# WattMeter.net
KiCad netlist of a schematic drawn in EAGLE
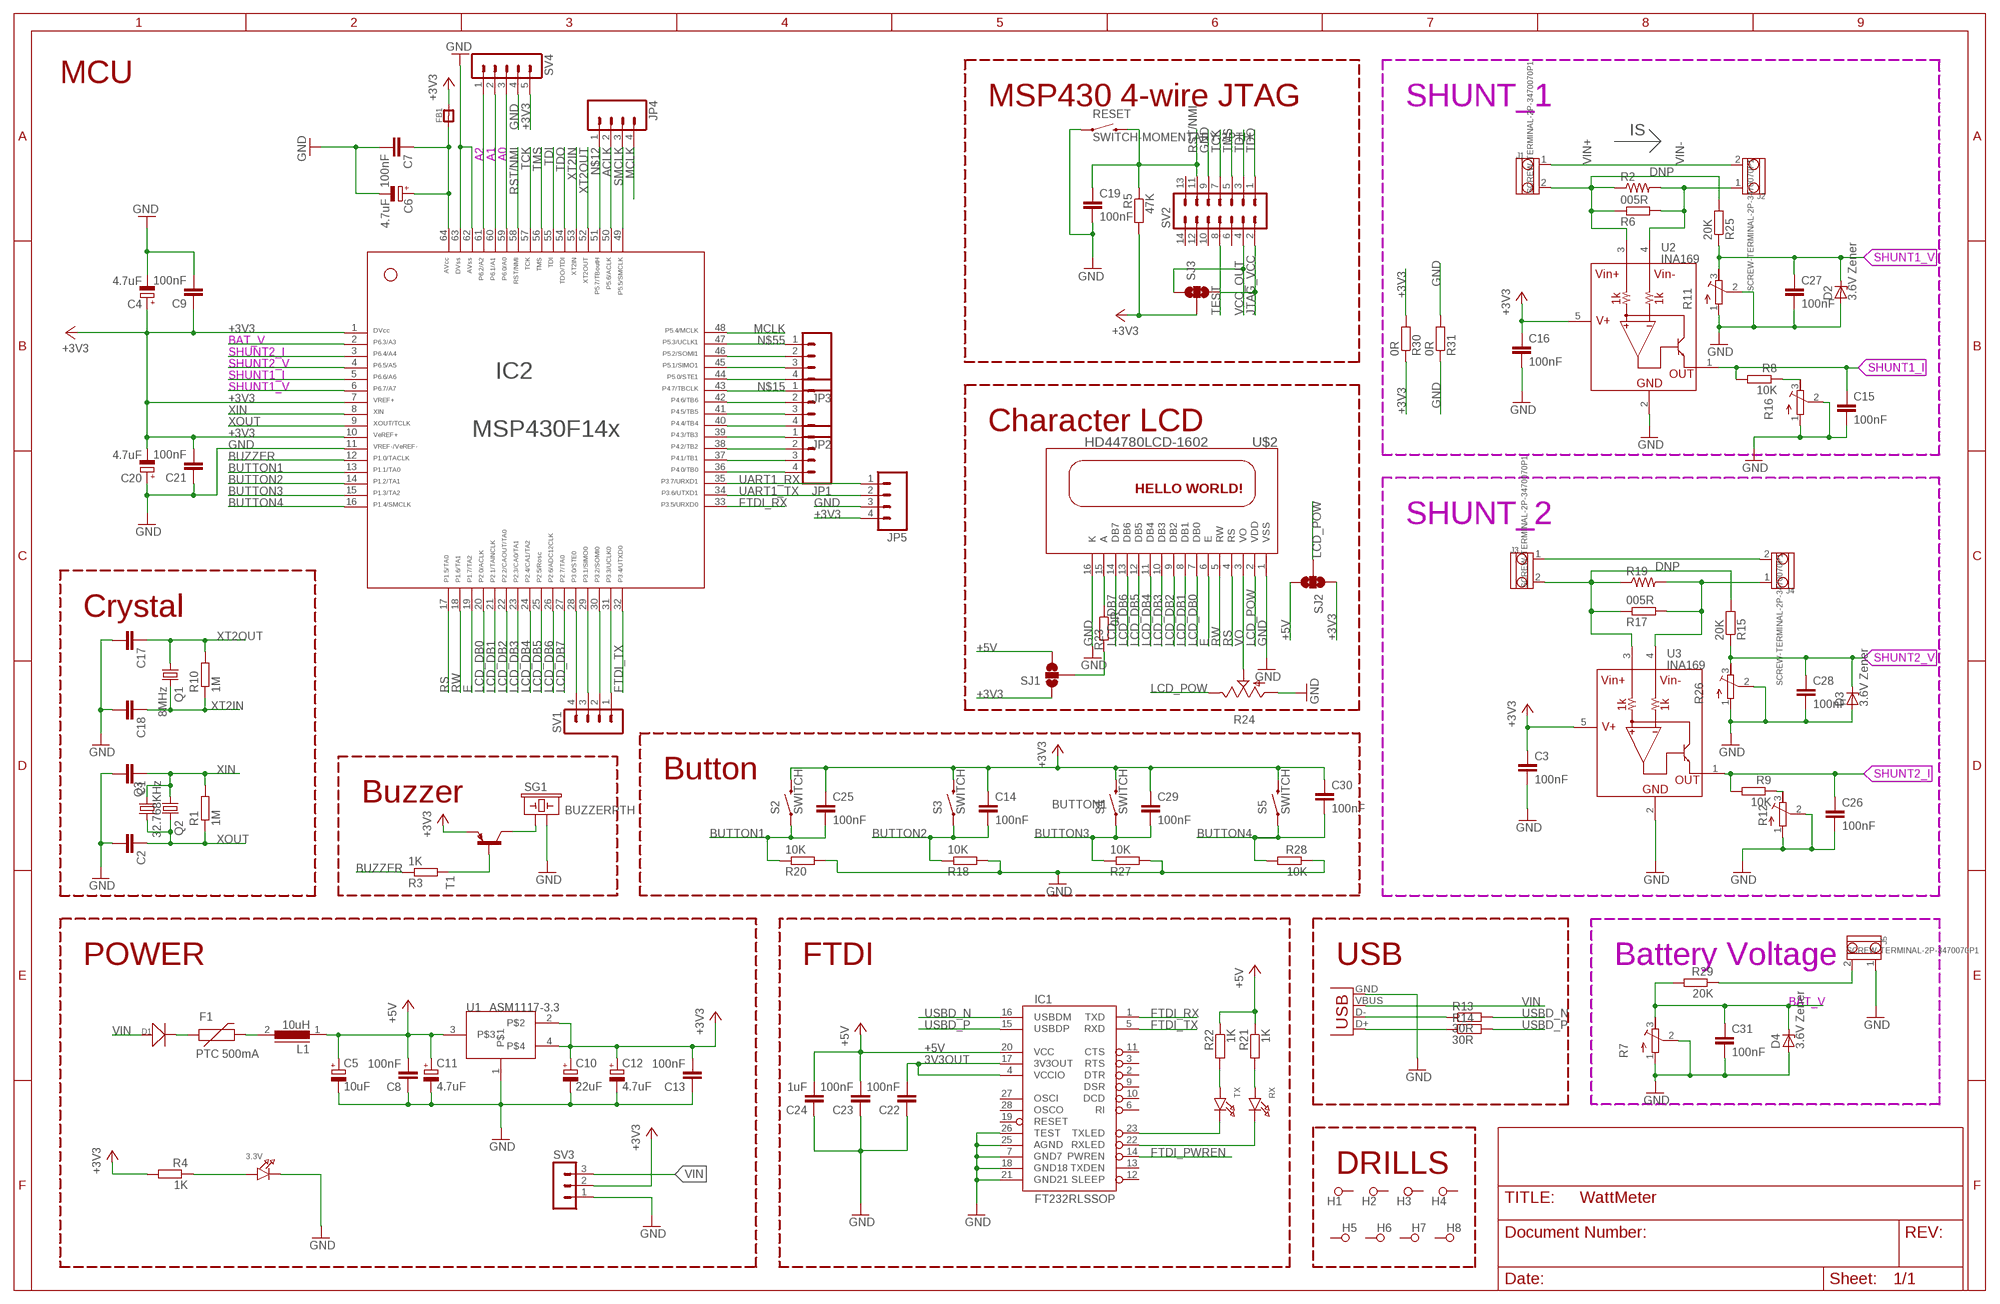
[diagram p0: schematic, sheet 1]

(export (version "E")
  (design (tool "Eeschema 10.0.6"))
  (components
    (comp (ref "3.3V")
      (value "LED0805")
      (footprint "eagle-import:CHIPLED_0805")
      (libsource (lib "eagle-import") (part "LED0805"))
    )
    (comp (ref "C1")
      (value "C-EUC0805")
      (footprint "eagle-import:C0805")
      (libsource (lib "eagle-import") (part "C-EUC0805"))
    )
    (comp (ref "C2")
      (value "C-EUC0805")
      (footprint "eagle-import:C0805")
      (libsource (lib "eagle-import") (part "C-EUC0805"))
    )
    (comp (ref "C3")
      (value "100nF")
      (footprint "eagle-import:C0805")
      (libsource (lib "eagle-import") (part "C-EUC0805"))
    )
    (comp (ref "C4")
      (value "4.7uF")
      (footprint "eagle-import:A_3216-18W")
      (libsource (lib "eagle-import") (part "CPOL-EUA/3216-18W"))
    )
    (comp (ref "C5")
      (value "10uF")
      (footprint "eagle-import:150CLZ-0810")
      (libsource (lib "eagle-import") (part "CPOL-EU150CLZ-0810"))
    )
    (comp (ref "C6")
      (value "4.7uF")
      (footprint "eagle-import:A_3216-18W")
      (libsource (lib "eagle-import") (part "CPOL-EUA/3216-18W"))
    )
    (comp (ref "C7")
      (value "100nF")
      (footprint "eagle-import:C0805")
      (libsource (lib "eagle-import") (part "C-EUC0805"))
    )
    (comp (ref "C8")
      (value "100nF")
      (footprint "eagle-import:C0805")
      (libsource (lib "eagle-import") (part "C-EUC0805"))
    )
    (comp (ref "C9")
      (value "100nF")
      (footprint "eagle-import:C0805")
      (libsource (lib "eagle-import") (part "C-EUC0805"))
    )
    (comp (ref "C10")
      (value "22uF")
      (footprint "eagle-import:B_3528-21R")
      (libsource (lib "eagle-import") (part "CPOL-EUB/3528-21R"))
    )
    (comp (ref "C11")
      (value "4.7uF")
      (footprint "eagle-import:A_3216-18W")
      (libsource (lib "eagle-import") (part "CPOL-EUA/3216-18W"))
    )
    (comp (ref "C12")
      (value "4.7uF")
      (footprint "eagle-import:A_3216-18W")
      (libsource (lib "eagle-import") (part "CPOL-EUA/3216-18W"))
    )
    (comp (ref "C13")
      (value "100nF")
      (footprint "eagle-import:C0805")
      (libsource (lib "eagle-import") (part "C-EUC0805"))
    )
    (comp (ref "C14")
      (value "100nF")
      (footprint "eagle-import:C0805")
      (libsource (lib "eagle-import") (part "C-EUC0805"))
    )
    (comp (ref "C15")
      (value "100nF")
      (footprint "eagle-import:C0805")
      (libsource (lib "eagle-import") (part "C-EUC0805"))
    )
    (comp (ref "C16")
      (value "100nF")
      (footprint "eagle-import:C0805")
      (libsource (lib "eagle-import") (part "C-EUC0805"))
    )
    (comp (ref "C17")
      (value "C-EUC0805")
      (footprint "eagle-import:C0805")
      (libsource (lib "eagle-import") (part "C-EUC0805"))
    )
    (comp (ref "C18")
      (value "C-EUC0805")
      (footprint "eagle-import:C0805")
      (libsource (lib "eagle-import") (part "C-EUC0805"))
    )
    (comp (ref "C19")
      (value "100nF")
      (footprint "eagle-import:C0805")
      (libsource (lib "eagle-import") (part "C-EUC0805"))
    )
    (comp (ref "C20")
      (value "4.7uF")
      (footprint "eagle-import:A_3216-18W")
      (libsource (lib "eagle-import") (part "CPOL-EUA/3216-18W"))
    )
    (comp (ref "C21")
      (value "100nF")
      (footprint "eagle-import:C0805")
      (libsource (lib "eagle-import") (part "C-EUC0805"))
    )
    (comp (ref "C22")
      (value "100nF")
      (footprint "eagle-import:C0805")
      (libsource (lib "eagle-import") (part "C-EUC0805"))
    )
    (comp (ref "C23")
      (value "100nF")
      (footprint "eagle-import:C0805")
      (libsource (lib "eagle-import") (part "C-EUC0805"))
    )
    (comp (ref "C24")
      (value "1uF")
      (footprint "eagle-import:C0805")
      (libsource (lib "eagle-import") (part "C-EUC0805"))
    )
    (comp (ref "C25")
      (value "100nF")
      (footprint "eagle-import:C0805")
      (libsource (lib "eagle-import") (part "C-EUC0805"))
    )
    (comp (ref "C26")
      (value "100nF")
      (footprint "eagle-import:C0805")
      (libsource (lib "eagle-import") (part "C-EUC0805"))
    )
    (comp (ref "C27")
      (value "100nF")
      (footprint "eagle-import:C0805")
      (libsource (lib "eagle-import") (part "C-EUC0805"))
    )
    (comp (ref "C28")
      (value "100nF")
      (footprint "eagle-import:C0805")
      (libsource (lib "eagle-import") (part "C-EUC0805"))
    )
    (comp (ref "C29")
      (value "100nF")
      (footprint "eagle-import:C0805")
      (libsource (lib "eagle-import") (part "C-EUC0805"))
    )
    (comp (ref "C30")
      (value "100nF")
      (footprint "eagle-import:C0805")
      (libsource (lib "eagle-import") (part "C-EUC0805"))
    )
    (comp (ref "C31")
      (value "100nF")
      (footprint "eagle-import:C0805")
      (libsource (lib "eagle-import") (part "C-EUC0805"))
    )
    (comp (ref "D1")
      (value "D-D1206")
      (footprint "eagle-import:LL-34")
      (libsource (lib "eagle-import") (part "D-D1206"))
    )
    (comp (ref "D2")
      (value "3.6V Zener")
      (footprint "eagle-import:SMB")
      (libsource (lib "eagle-import") (part "ZENER-DIODESMB"))
    )
    (comp (ref "D3")
      (value "3.6V Zener")
      (footprint "eagle-import:SMB")
      (libsource (lib "eagle-import") (part "ZENER-DIODESMB"))
    )
    (comp (ref "D4")
      (value "3.6V Zener")
      (footprint "eagle-import:SMB")
      (libsource (lib "eagle-import") (part "ZENER-DIODESMB"))
    )
    (comp (ref "F1")
      (value "PTC 500mA")
      (footprint "eagle-import:PTC-1206")
      (libsource (lib "eagle-import") (part "PTCSMD"))
    )
    (comp (ref "FB1")
      (value "FERRITE0805")
      (footprint "eagle-import:0805")
      (libsource (lib "eagle-import") (part "FERRITE0805"))
    )
    (comp (ref "H1")
      (value "SPECIAL_DRILL_0.1000")
      (footprint "eagle-import:PAD_0.1000")
      (libsource (lib "eagle-import") (part "SPECIAL_DRILL_0.1000"))
    )
    (comp (ref "H2")
      (value "SPECIAL_DRILL_0.1000")
      (footprint "eagle-import:PAD_0.1000")
      (libsource (lib "eagle-import") (part "SPECIAL_DRILL_0.1000"))
    )
    (comp (ref "H3")
      (value "SPECIAL_DRILL_0.1000")
      (footprint "eagle-import:PAD_0.1000")
      (libsource (lib "eagle-import") (part "SPECIAL_DRILL_0.1000"))
    )
    (comp (ref "H4")
      (value "SPECIAL_DRILL_0.1000")
      (footprint "eagle-import:PAD_0.1000")
      (libsource (lib "eagle-import") (part "SPECIAL_DRILL_0.1000"))
    )
    (comp (ref "H5")
      (value "SPECIAL_DRILL_0.1000")
      (footprint "eagle-import:PAD_0.1000")
      (libsource (lib "eagle-import") (part "SPECIAL_DRILL_0.1000"))
    )
    (comp (ref "H6")
      (value "SPECIAL_DRILL_0.1000")
      (footprint "eagle-import:PAD_0.1000")
      (libsource (lib "eagle-import") (part "SPECIAL_DRILL_0.1000"))
    )
    (comp (ref "H7")
      (value "SPECIAL_DRILL_0.1000")
      (footprint "eagle-import:PAD_0.1000")
      (libsource (lib "eagle-import") (part "SPECIAL_DRILL_0.1000"))
    )
    (comp (ref "H8")
      (value "SPECIAL_DRILL_0.1000")
      (footprint "eagle-import:PAD_0.1000")
      (libsource (lib "eagle-import") (part "SPECIAL_DRILL_0.1000"))
    )
    (comp (ref "IC1")
      (value "FT232RLSSOP")
      (footprint "eagle-import:SSOP28DB")
      (libsource (lib "eagle-import") (part "FT232RLSSOP"))
    )
    (comp (ref "IC2")
      (value "F14X---PM/PAG64")
      (footprint "eagle-import:PM_PAG64")
      (libsource (lib "eagle-import") (part "F14X---PM/PAG64"))
    )
    (comp (ref "J1")
      (value "SCREW-TERMINAL-2P-3470070P1")
      (footprint "eagle-import:2P-3.5")
      (libsource (lib "eagle-import") (part "SCREW-TERMINAL-2P-3470070P1"))
    )
    (comp (ref "J2")
      (value "SCREW-TERMINAL-2P-3470070P1")
      (footprint "eagle-import:2P-3.5")
      (libsource (lib "eagle-import") (part "SCREW-TERMINAL-2P-3470070P1"))
    )
    (comp (ref "J3")
      (value "SCREW-TERMINAL-2P-3470070P1")
      (footprint "eagle-import:2P-3.5")
      (libsource (lib "eagle-import") (part "SCREW-TERMINAL-2P-3470070P1"))
    )
    (comp (ref "J4")
      (value "SCREW-TERMINAL-2P-3470070P1")
      (footprint "eagle-import:2P-3.5")
      (libsource (lib "eagle-import") (part "SCREW-TERMINAL-2P-3470070P1"))
    )
    (comp (ref "J5")
      (value "SCREW-TERMINAL-2P-3470070P1")
      (footprint "eagle-import:2P-3.5")
      (libsource (lib "eagle-import") (part "SCREW-TERMINAL-2P-3470070P1"))
    )
    (comp (ref "JP1")
      (value "M041.27MM")
      (footprint "eagle-import:1X04-1.27MM")
      (libsource (lib "eagle-import") (part "M041.27MM"))
    )
    (comp (ref "JP2")
      (value "M041.27MM")
      (footprint "eagle-import:1X04-1.27MM")
      (libsource (lib "eagle-import") (part "M041.27MM"))
    )
    (comp (ref "JP3")
      (value "M041.27MM")
      (footprint "eagle-import:1X04-1.27MM")
      (libsource (lib "eagle-import") (part "M041.27MM"))
    )
    (comp (ref "JP4")
      (value "M041.27MM")
      (footprint "eagle-import:1X04-1.27MM")
      (libsource (lib "eagle-import") (part "M041.27MM"))
    )
    (comp (ref "JP5")
      (value "M041.27MM")
      (footprint "eagle-import:1X04-1.27MM")
      (libsource (lib "eagle-import") (part "M041.27MM"))
    )
    (comp (ref "L1")
      (value "10uH")
      (footprint "eagle-import:DR74")
      (libsource (lib "eagle-import") (part "DR74"))
    )
    (comp (ref "Q1")
      (value "8MHz")
      (footprint "eagle-import:HC49U-V")
      (libsource (lib "eagle-import") (part "CRYSTALHC49U-V"))
    )
    (comp (ref "Q2")
      (value "32.768KHz")
      (footprint "eagle-import:HC49U-V")
      (libsource (lib "eagle-import") (part "CRYSTALHC49U-V"))
    )
    (comp (ref "Q3")
      (value "CRYSTALTC38H")
      (footprint "eagle-import:TC38H")
      (libsource (lib "eagle-import") (part "CRYSTALTC38H"))
    )
    (comp (ref "R1")
      (value "1M")
      (footprint "eagle-import:R0805")
      (libsource (lib "eagle-import") (part "R-EU_R0805"))
    )
    (comp (ref "R2")
      (value "RESISTORPTH-2W")
      (footprint "eagle-import:AXIAL-0.8")
      (fields (field (name "PLACE") "DNP"))
      (libsource (lib "eagle-import") (part "RESISTORPTH-2W"))
    )
    (comp (ref "R3")
      (value "1K")
      (footprint "eagle-import:R0805")
      (libsource (lib "eagle-import") (part "R-EU_R0805"))
    )
    (comp (ref "R4")
      (value "1K")
      (footprint "eagle-import:R0805")
      (libsource (lib "eagle-import") (part "R-EU_R0805"))
    )
    (comp (ref "R5")
      (value "47K")
      (footprint "eagle-import:R0805")
      (libsource (lib "eagle-import") (part "R-EU_R0805"))
    )
    (comp (ref "R6")
      (value "005R")
      (footprint "eagle-import:R2512")
      (libsource (lib "eagle-import") (part "R-EU_R2512"))
    )
    (comp (ref "R7")
      (value "R-TRIMM3296W")
      (footprint "eagle-import:RTRIM3296W")
      (libsource (lib "eagle-import") (part "R-TRIMM3296W"))
    )
    (comp (ref "R8")
      (value "10K")
      (footprint "eagle-import:R0805")
      (libsource (lib "eagle-import") (part "R-EU_R0805"))
    )
    (comp (ref "R9")
      (value "10K")
      (footprint "eagle-import:R0805")
      (libsource (lib "eagle-import") (part "R-EU_R0805"))
    )
    (comp (ref "R10")
      (value "1M")
      (footprint "eagle-import:R0805")
      (libsource (lib "eagle-import") (part "R-EU_R0805"))
    )
    (comp (ref "R11")
      (value "R-TRIMM3296W")
      (footprint "eagle-import:RTRIM3296W")
      (libsource (lib "eagle-import") (part "R-TRIMM3296W"))
    )
    (comp (ref "R12")
      (value "R-TRIMM3296W")
      (footprint "eagle-import:RTRIM3296W")
      (libsource (lib "eagle-import") (part "R-TRIMM3296W"))
    )
    (comp (ref "R13")
      (value "30R")
      (footprint "eagle-import:R0805")
      (libsource (lib "eagle-import") (part "R-EU_R0805"))
    )
    (comp (ref "R14")
      (value "30R")
      (footprint "eagle-import:R0805")
      (libsource (lib "eagle-import") (part "R-EU_R0805"))
    )
    (comp (ref "R15")
      (value "20K")
      (footprint "eagle-import:R0805")
      (libsource (lib "eagle-import") (part "R-EU_R0805"))
    )
    (comp (ref "R16")
      (value "R-TRIMM3296W")
      (footprint "eagle-import:RTRIM3296W")
      (libsource (lib "eagle-import") (part "R-TRIMM3296W"))
    )
    (comp (ref "R17")
      (value "005R")
      (footprint "eagle-import:R2512")
      (libsource (lib "eagle-import") (part "R-EU_R2512"))
    )
    (comp (ref "R18")
      (value "10K")
      (footprint "eagle-import:R0805")
      (libsource (lib "eagle-import") (part "R-EU_R0805"))
    )
    (comp (ref "R19")
      (value "RESISTORPTH-2W")
      (footprint "eagle-import:AXIAL-0.8")
      (fields (field (name "PLACE") "DNP"))
      (libsource (lib "eagle-import") (part "RESISTORPTH-2W"))
    )
    (comp (ref "R20")
      (value "10K")
      (footprint "eagle-import:R0805")
      (libsource (lib "eagle-import") (part "R-EU_R0805"))
    )
    (comp (ref "R21")
      (value "1K")
      (footprint "eagle-import:R0805")
      (libsource (lib "eagle-import") (part "R-EU_R0805"))
    )
    (comp (ref "R22")
      (value "1K")
      (footprint "eagle-import:R0805")
      (libsource (lib "eagle-import") (part "R-EU_R0805"))
    )
    (comp (ref "R23")
      (value "0R")
      (footprint "eagle-import:R0805")
      (libsource (lib "eagle-import") (part "R-EU_R0805"))
    )
    (comp (ref "R24")
      (value "TRIM_US-3223G")
      (footprint "eagle-import:3223G")
      (libsource (lib "eagle-import") (part "TRIM_US-3223G"))
    )
    (comp (ref "R25")
      (value "20K")
      (footprint "eagle-import:R0805")
      (libsource (lib "eagle-import") (part "R-EU_R0805"))
    )
    (comp (ref "R26")
      (value "R-TRIMM3296W")
      (footprint "eagle-import:RTRIM3296W")
      (libsource (lib "eagle-import") (part "R-TRIMM3296W"))
    )
    (comp (ref "R27")
      (value "10K")
      (footprint "eagle-import:R0805")
      (libsource (lib "eagle-import") (part "R-EU_R0805"))
    )
    (comp (ref "R28")
      (value "10K")
      (footprint "eagle-import:R0805")
      (libsource (lib "eagle-import") (part "R-EU_R0805"))
    )
    (comp (ref "R29")
      (value "20K")
      (footprint "eagle-import:R0805")
      (libsource (lib "eagle-import") (part "R-EU_R0805"))
    )
    (comp (ref "R30")
      (value "0R")
      (footprint "eagle-import:R1206")
      (libsource (lib "eagle-import") (part "R-EU_R1206"))
    )
    (comp (ref "R31")
      (value "0R")
      (footprint "eagle-import:R1206")
      (libsource (lib "eagle-import") (part "R-EU_R1206"))
    )
    (comp (ref "RESET")
      (value "SWITCH-MOMENTARY-2PTH")
      (footprint "eagle-import:TACTILE-PTH")
      (libsource (lib "eagle-import") (part "SWITCH-MOMENTARY-2PTH"))
    )
    (comp (ref "RX")
      (value "LED0805")
      (footprint "eagle-import:CHIPLED_0805")
      (libsource (lib "eagle-import") (part "LED0805"))
    )
    (comp (ref "S2")
      (value "SWITCH")
      (footprint "eagle-import:TACTILE-PTH")
      (libsource (lib "eagle-import") (part "SWITCH-MOMENTARY-2PTH"))
    )
    (comp (ref "S3")
      (value "SWITCH")
      (footprint "eagle-import:TACTILE-PTH")
      (libsource (lib "eagle-import") (part "SWITCH-MOMENTARY-2PTH"))
    )
    (comp (ref "S4")
      (value "SWITCH")
      (footprint "eagle-import:TACTILE-PTH")
      (libsource (lib "eagle-import") (part "SWITCH-MOMENTARY-2PTH"))
    )
    (comp (ref "S5")
      (value "SWITCH")
      (footprint "eagle-import:TACTILE-PTH")
      (libsource (lib "eagle-import") (part "SWITCH-MOMENTARY-2PTH"))
    )
    (comp (ref "SG1")
      (value "BUZZERPTH")
      (footprint "eagle-import:BUZZER-12MM")
      (libsource (lib "eagle-import") (part "BUZZERPTH"))
    )
    (comp (ref "SJ1")
      (value "SOLDERJUMPER_2WAYS")
      (footprint "eagle-import:SJ_3")
      (libsource (lib "eagle-import") (part "SOLDERJUMPER_2WAYS"))
    )
    (comp (ref "SJ2")
      (value "SOLDERJUMPER_2WAYS")
      (footprint "eagle-import:SJ_3")
      (libsource (lib "eagle-import") (part "SOLDERJUMPER_2WAYS"))
    )
    (comp (ref "SJ3")
      (value "SOLDERJUMPER_2WAYS")
      (footprint "eagle-import:SJ_3")
      (libsource (lib "eagle-import") (part "SOLDERJUMPER_2WAYS"))
    )
    (comp (ref "SV1")
      (value "MA04-1")
      (footprint "eagle-import:MA04-1")
      (libsource (lib "eagle-import") (part "MA04-1"))
    )
    (comp (ref "SV2")
      (value "ML14L")
      (footprint "eagle-import:ML14L")
      (libsource (lib "eagle-import") (part "ML14L"))
    )
    (comp (ref "SV3")
      (value "MA03-1")
      (footprint "eagle-import:MA03-1")
      (fields (field (name "OC_FARNELL") "unknown") (field (name "OC_NEWARK") "unknown"))
      (libsource (lib "eagle-import") (part "MA03-1"))
    )
    (comp (ref "SV4")
      (value "MA05-1")
      (footprint "eagle-import:MA05-1")
      (libsource (lib "eagle-import") (part "MA05-1"))
    )
    (comp (ref "T1")
      (value "MMBT3906LT1-PNP-SOT23-BEC")
      (footprint "eagle-import:SOT23-BEC")
      (libsource (lib "eagle-import") (part "-PNP-SOT23-BECMMBT3906LT1"))
    )
    (comp (ref "TX")
      (value "LED0805")
      (footprint "eagle-import:CHIPLED_0805")
      (libsource (lib "eagle-import") (part "LED0805"))
    )
    (comp (ref "U$2")
      (value "HD44780LCD-1602")
      (footprint "eagle-import:LCD1602")
      (libsource (lib "eagle-import") (part "HD44780LCD-1602"))
    )
    (comp (ref "U1")
      (value "ASM1117-3.3")
      (footprint "eagle-import:SOT223")
      (libsource (lib "eagle-import") (part "ASM1117-3.3"))
    )
    (comp (ref "U2")
      (value "INA169")
      (footprint "eagle-import:SOT23-5")
      (libsource (lib "eagle-import") (part "INA169"))
    )
    (comp (ref "U3")
      (value "INA169")
      (footprint "eagle-import:SOT23-5")
      (libsource (lib "eagle-import") (part "INA169"))
    )
    (comp (ref "X2")
      (value "USBPTH")
      (footprint "eagle-import:USB-B-PTH")
      (libsource (lib "eagle-import") (part "USBPTH"))
    )
  )
  (nets
    (net (code "1") (name "+3V3") (class "Default")
      (node (ref "C10") (pin "+") (pinfunction "+_+") (pintype "passive"))
      (node (ref "C12") (pin "+") (pinfunction "+_+") (pintype "passive"))
      (node (ref "C13") (pin "2") (pinfunction "2_2") (pintype "passive"))
      (node (ref "C14") (pin "1") (pinfunction "1_1") (pintype "passive"))
      (node (ref "C16") (pin "1") (pinfunction "1_1") (pintype "passive"))
      (node (ref "C20") (pin "-") (pinfunction "-_-") (pintype "passive"))
      (node (ref "C21") (pin "2") (pinfunction "2_2") (pintype "passive"))
      (node (ref "C25") (pin "1") (pinfunction "1_1") (pintype "passive"))
      (node (ref "C29") (pin "1") (pinfunction "1_1") (pintype "passive"))
      (node (ref "C3") (pin "1") (pinfunction "1_1") (pintype "passive"))
      (node (ref "C30") (pin "1") (pinfunction "1_1") (pintype "passive"))
      (node (ref "C4") (pin "+") (pinfunction "+_+") (pintype "passive"))
      (node (ref "C9") (pin "1") (pinfunction "1_1") (pintype "passive"))
      (node (ref "FB1") (pin "1") (pinfunction "P$1_1") (pintype "passive"))
      (node (ref "IC2") (pin "1") (pinfunction "1_1") (pintype "power_in"))
      (node (ref "IC2") (pin "10") (pinfunction "10_10") (pintype "input"))
      (node (ref "IC2") (pin "7") (pinfunction "7_7") (pintype "output"))
      (node (ref "JP5") (pin "4") (pinfunction "4_4") (pintype "passive"))
      (node (ref "R30") (pin "1") (pinfunction "1_1") (pintype "passive"))
      (node (ref "R30") (pin "2") (pinfunction "2_2") (pintype "passive"))
      (node (ref "R4") (pin "2") (pinfunction "2_2") (pintype "passive"))
      (node (ref "R5") (pin "2") (pinfunction "2_2") (pintype "passive"))
      (node (ref "S2") (pin "3") (pinfunction "2_3") (pintype "passive"))
      (node (ref "S3") (pin "3") (pinfunction "2_3") (pintype "passive"))
      (node (ref "S4") (pin "3") (pinfunction "2_3") (pintype "passive"))
      (node (ref "S5") (pin "3") (pinfunction "2_3") (pintype "passive"))
      (node (ref "SJ1") (pin "1") (pinfunction "1_1") (pintype "passive"))
      (node (ref "SJ2") (pin "1") (pinfunction "1_1") (pintype "passive"))
      (node (ref "SJ3") (pin "2") (pinfunction "2_2") (pintype "passive"))
      (node (ref "SV3") (pin "2") (pinfunction "2_2") (pintype "passive"))
      (node (ref "SV4") (pin "5") (pinfunction "5_5") (pintype "passive"))
      (node (ref "T1") (pin "E") (pinfunction "E_E") (pintype "passive"))
      (node (ref "U1") (pin "2") (pinfunction "P$2_2") (pintype "bidirectional"))
      (node (ref "U1") (pin "4") (pinfunction "P$4_4") (pintype "bidirectional"))
      (node (ref "U2") (pin "5") (pinfunction "V+_5") (pintype "bidirectional"))
      (node (ref "U3") (pin "5") (pinfunction "V+_5") (pintype "bidirectional"))
    )
    (net (code "2") (name "+5V") (class "Default")
      (node (ref "C11") (pin "+") (pinfunction "+_+") (pintype "passive"))
      (node (ref "C23") (pin "2") (pinfunction "2_2") (pintype "passive"))
      (node (ref "C24") (pin "2") (pinfunction "2_2") (pintype "passive"))
      (node (ref "C5") (pin "+") (pinfunction "+_+") (pintype "passive"))
      (node (ref "C8") (pin "2") (pinfunction "2_2") (pintype "passive"))
      (node (ref "IC1") (pin "20") (pinfunction "VCC_20") (pintype "power_in"))
      (node (ref "L1") (pin "1") (pinfunction "1_1") (pintype "passive"))
      (node (ref "R21") (pin "1") (pinfunction "1_1") (pintype "passive"))
      (node (ref "R22") (pin "1") (pinfunction "1_1") (pintype "passive"))
      (node (ref "SJ1") (pin "3") (pinfunction "3_3") (pintype "passive"))
      (node (ref "SJ2") (pin "3") (pinfunction "3_3") (pintype "passive"))
      (node (ref "U1") (pin "3") (pinfunction "P$3_3") (pintype "bidirectional"))
    )
    (net (code "3") (name "/3V3OUT") (class "Default")
      (node (ref "C22") (pin "2") (pinfunction "2_2") (pintype "passive"))
      (node (ref "IC1") (pin "17") (pinfunction "3V3OUT_17") (pintype "output"))
      (node (ref "IC1") (pin "4") (pinfunction "VCCIO_4") (pintype "power_in"))
    )
    (net (code "4") (name "/A0") (class "Default")
      (node (ref "IC2") (pin "59") (pinfunction "59_59") (pintype "bidirectional"))
      (node (ref "SV4") (pin "3") (pinfunction "3_3") (pintype "passive"))
    )
    (net (code "5") (name "/A1") (class "Default")
      (node (ref "IC2") (pin "60") (pinfunction "60_60") (pintype "bidirectional"))
      (node (ref "SV4") (pin "2") (pinfunction "2_2") (pintype "passive"))
    )
    (net (code "6") (name "/A2") (class "Default")
      (node (ref "IC2") (pin "61") (pinfunction "61_61") (pintype "bidirectional"))
      (node (ref "SV4") (pin "1") (pinfunction "1_1") (pintype "passive"))
    )
    (net (code "7") (name "/ACLK") (class "Default")
      (node (ref "IC2") (pin "50") (pinfunction "50_50") (pintype "bidirectional"))
      (node (ref "JP4") (pin "2") (pinfunction "2_2") (pintype "passive"))
    )
    (net (code "8") (name "/BAT_V") (class "Default")
      (node (ref "C31") (pin "1") (pinfunction "1_1") (pintype "passive"))
      (node (ref "D4") (pin "C") (pinfunction "C_C") (pintype "passive"))
      (node (ref "IC2") (pin "2") (pinfunction "2_2") (pintype "bidirectional"))
      (node (ref "R29") (pin "2") (pinfunction "2_2") (pintype "passive"))
      (node (ref "R7") (pin "3") (pinfunction "E_3") (pintype "passive"))
    )
    (net (code "9") (name "/BUTTON1") (class "Default")
      (node (ref "C25") (pin "2") (pinfunction "2_2") (pintype "passive"))
      (node (ref "IC2") (pin "13") (pinfunction "13_13") (pintype "bidirectional"))
      (node (ref "R20") (pin "1") (pinfunction "1_1") (pintype "passive"))
      (node (ref "S2") (pin "1") (pinfunction "1_1") (pintype "passive"))
    )
    (net (code "10") (name "/BUTTON2") (class "Default")
      (node (ref "C14") (pin "2") (pinfunction "2_2") (pintype "passive"))
      (node (ref "IC2") (pin "14") (pinfunction "14_14") (pintype "bidirectional"))
      (node (ref "R18") (pin "1") (pinfunction "1_1") (pintype "passive"))
      (node (ref "S3") (pin "1") (pinfunction "1_1") (pintype "passive"))
    )
    (net (code "11") (name "/BUTTON3") (class "Default")
      (node (ref "C29") (pin "2") (pinfunction "2_2") (pintype "passive"))
      (node (ref "IC2") (pin "15") (pinfunction "15_15") (pintype "bidirectional"))
      (node (ref "R27") (pin "1") (pinfunction "1_1") (pintype "passive"))
      (node (ref "S4") (pin "1") (pinfunction "1_1") (pintype "passive"))
    )
    (net (code "12") (name "/BUTTON4") (class "Default")
      (node (ref "C30") (pin "2") (pinfunction "2_2") (pintype "passive"))
      (node (ref "IC2") (pin "16") (pinfunction "16_16") (pintype "bidirectional"))
      (node (ref "R28") (pin "2") (pinfunction "2_2") (pintype "passive"))
      (node (ref "S5") (pin "1") (pinfunction "1_1") (pintype "passive"))
    )
    (net (code "13") (name "/BUZZER") (class "Default")
      (node (ref "IC2") (pin "12") (pinfunction "12_12") (pintype "bidirectional"))
      (node (ref "R3") (pin "1") (pinfunction "1_1") (pintype "passive"))
    )
    (net (code "14") (name "/E") (class "Default")
      (node (ref "IC2") (pin "19") (pinfunction "19_19") (pintype "bidirectional"))
      (node (ref "U$2") (pin "6") (pinfunction "E_6") (pintype "input"))
    )
    (net (code "15") (name "/FTDI_PWREN") (class "Default")
      (node (ref "IC1") (pin "14") (pinfunction "PWREN_14") (pintype "input"))
    )
    (net (code "16") (name "/FTDI_RX") (class "Default")
      (node (ref "IC1") (pin "1") (pinfunction "TXD_1") (pintype "output"))
      (node (ref "IC2") (pin "33") (pinfunction "33_33") (pintype "bidirectional"))
    )
    (net (code "17") (name "/FTDI_TX") (class "Default")
      (node (ref "IC1") (pin "5") (pinfunction "RXD_5") (pintype "input"))
      (node (ref "IC2") (pin "32") (pinfunction "32_32") (pintype "bidirectional"))
    )
    (net (code "18") (name "/JTAG_VCC") (class "Default")
      (node (ref "SJ3") (pin "3") (pinfunction "3_3") (pintype "passive"))
      (node (ref "SV2") (pin "2") (pinfunction "2_2") (pintype "passive"))
    )
    (net (code "19") (name "/LCD_DB0") (class "Default")
      (node (ref "IC2") (pin "20") (pinfunction "20_20") (pintype "bidirectional"))
      (node (ref "U$2") (pin "7") (pinfunction "DB0_7") (pintype "bidirectional"))
    )
    (net (code "20") (name "/LCD_DB1") (class "Default")
      (node (ref "IC2") (pin "21") (pinfunction "21_21") (pintype "bidirectional"))
      (node (ref "U$2") (pin "8") (pinfunction "DB1_8") (pintype "bidirectional"))
    )
    (net (code "21") (name "/LCD_DB2") (class "Default")
      (node (ref "IC2") (pin "22") (pinfunction "22_22") (pintype "bidirectional"))
      (node (ref "U$2") (pin "9") (pinfunction "DB2_9") (pintype "bidirectional"))
    )
    (net (code "22") (name "/LCD_DB3") (class "Default")
      (node (ref "IC2") (pin "23") (pinfunction "23_23") (pintype "bidirectional"))
      (node (ref "U$2") (pin "10") (pinfunction "DB3_10") (pintype "bidirectional"))
    )
    (net (code "23") (name "/LCD_DB4") (class "Default")
      (node (ref "IC2") (pin "24") (pinfunction "24_24") (pintype "bidirectional"))
      (node (ref "U$2") (pin "11") (pinfunction "DB4_11") (pintype "bidirectional"))
    )
    (net (code "24") (name "/LCD_DB5") (class "Default")
      (node (ref "IC2") (pin "25") (pinfunction "25_25") (pintype "bidirectional"))
      (node (ref "U$2") (pin "12") (pinfunction "DB5_12") (pintype "bidirectional"))
    )
    (net (code "25") (name "/LCD_DB6") (class "Default")
      (node (ref "IC2") (pin "26") (pinfunction "26_26") (pintype "bidirectional"))
      (node (ref "U$2") (pin "13") (pinfunction "DB6_13") (pintype "bidirectional"))
    )
    (net (code "26") (name "/LCD_DB7") (class "Default")
      (node (ref "IC2") (pin "27") (pinfunction "27_27") (pintype "bidirectional"))
      (node (ref "U$2") (pin "14") (pinfunction "DB7_14") (pintype "bidirectional"))
    )
    (net (code "27") (name "/LCD_POW") (class "Default")
      (node (ref "R24") (pin "3") (pinfunction "E_3") (pintype "passive"))
      (node (ref "SJ2") (pin "2") (pinfunction "2_2") (pintype "passive"))
      (node (ref "U$2") (pin "2") (pinfunction "VDD_2") (pintype "power_in"))
    )
    (net (code "28") (name "/MCLK") (class "Default")
      (node (ref "IC2") (pin "48") (pinfunction "48_48") (pintype "bidirectional"))
      (node (ref "JP4") (pin "4") (pinfunction "4_4") (pintype "passive"))
    )
    (net (code "29") (name "/N$12") (class "Default")
      (node (ref "IC2") (pin "51") (pinfunction "51_51") (pintype "bidirectional"))
      (node (ref "JP4") (pin "1") (pinfunction "1_1") (pintype "passive"))
    )
    (net (code "30") (name "/N$15") (class "Default")
      (node (ref "IC2") (pin "43") (pinfunction "43_43") (pintype "bidirectional"))
      (node (ref "JP2") (pin "1") (pinfunction "1_1") (pintype "passive"))
    )
    (net (code "31") (name "/N$55") (class "Default")
      (node (ref "IC2") (pin "47") (pinfunction "47_47") (pintype "bidirectional"))
      (node (ref "JP3") (pin "1") (pinfunction "1_1") (pintype "passive"))
    )
    (net (code "32") (name "/RS") (class "Default")
      (node (ref "IC2") (pin "17") (pinfunction "17_17") (pintype "bidirectional"))
      (node (ref "U$2") (pin "4") (pinfunction "RS_4") (pintype "input"))
    )
    (net (code "33") (name "/RST{slash}NMI") (class "Default")
      (node (ref "C19") (pin "1") (pinfunction "1_1") (pintype "passive"))
      (node (ref "IC2") (pin "58") (pinfunction "58_58") (pintype "input"))
      (node (ref "R5") (pin "1") (pinfunction "1_1") (pintype "passive"))
      (node (ref "RESET") (pin "3") (pinfunction "2_3") (pintype "passive"))
      (node (ref "SV2") (pin "11") (pinfunction "11_11") (pintype "passive"))
    )
    (net (code "34") (name "/RW") (class "Default")
      (node (ref "IC2") (pin "18") (pinfunction "18_18") (pintype "bidirectional"))
      (node (ref "U$2") (pin "5") (pinfunction "RW_5") (pintype "input"))
    )
    (net (code "35") (name "/SMCLK") (class "Default")
      (node (ref "IC2") (pin "49") (pinfunction "49_49") (pintype "bidirectional"))
      (node (ref "JP4") (pin "3") (pinfunction "3_3") (pintype "passive"))
    )
    (net (code "36") (name "/TCK") (class "Default")
      (node (ref "IC2") (pin "57") (pinfunction "57_57") (pintype "input"))
      (node (ref "SV2") (pin "7") (pinfunction "7_7") (pintype "passive"))
    )
    (net (code "37") (name "/TDI") (class "Default")
      (node (ref "IC2") (pin "55") (pinfunction "55_55") (pintype "input"))
      (node (ref "SV2") (pin "3") (pinfunction "3_3") (pintype "passive"))
    )
    (net (code "38") (name "/TDO") (class "Default")
      (node (ref "IC2") (pin "54") (pinfunction "54_54") (pintype "bidirectional"))
      (node (ref "SV2") (pin "1") (pinfunction "1_1") (pintype "passive"))
    )
    (net (code "39") (name "/TEST") (class "Default")
      (node (ref "SV2") (pin "8") (pinfunction "8_8") (pintype "passive"))
    )
    (net (code "40") (name "/TMS") (class "Default")
      (node (ref "IC2") (pin "56") (pinfunction "56_56") (pintype "input"))
      (node (ref "SV2") (pin "5") (pinfunction "5_5") (pintype "passive"))
    )
    (net (code "41") (name "/UART1_RX") (class "Default")
      (node (ref "IC2") (pin "35") (pinfunction "35_35") (pintype "bidirectional"))
      (node (ref "JP5") (pin "1") (pinfunction "1_1") (pintype "passive"))
    )
    (net (code "42") (name "/UART1_TX") (class "Default")
      (node (ref "IC2") (pin "34") (pinfunction "34_34") (pintype "bidirectional"))
      (node (ref "JP5") (pin "2") (pinfunction "2_2") (pintype "passive"))
    )
    (net (code "43") (name "/USBD_N") (class "Default")
      (node (ref "IC1") (pin "16") (pinfunction "USBDM_16") (pintype "bidirectional"))
      (node (ref "R13") (pin "2") (pinfunction "2_2") (pintype "passive"))
    )
    (net (code "44") (name "/USBD_P") (class "Default")
      (node (ref "IC1") (pin "15") (pinfunction "USBDP_15") (pintype "bidirectional"))
      (node (ref "R14") (pin "2") (pinfunction "2_2") (pintype "passive"))
    )
    (net (code "45") (name "/VCC_OUT") (class "Default")
      (node (ref "SJ3") (pin "1") (pinfunction "1_1") (pintype "passive"))
      (node (ref "SV2") (pin "4") (pinfunction "4_4") (pintype "passive"))
    )
    (net (code "46") (name "/VIN+") (class "Default")
      (node (ref "J1") (pin "2") (pinfunction "2_2") (pintype "bidirectional"))
      (node (ref "R2") (pin "P$1") (pinfunction "1_P$1") (pintype "passive"))
      (node (ref "R25") (pin "2") (pinfunction "2_2") (pintype "passive"))
      (node (ref "R6") (pin "1") (pinfunction "1_1") (pintype "passive"))
      (node (ref "U2") (pin "3") (pinfunction "VIN+_3") (pintype "bidirectional"))
    )
    (net (code "47") (name "/VIN-") (class "Default")
      (node (ref "J2") (pin "1") (pinfunction "1_1") (pintype "bidirectional"))
      (node (ref "R2") (pin "P$2") (pinfunction "2_P$2") (pintype "passive"))
      (node (ref "R6") (pin "2") (pinfunction "2_2") (pintype "passive"))
      (node (ref "U2") (pin "4") (pinfunction "VIN-_4") (pintype "bidirectional"))
    )
    (net (code "48") (name "/VO") (class "Default")
      (node (ref "R24") (pin "2") (pinfunction "S_2") (pintype "passive"))
      (node (ref "U$2") (pin "3") (pinfunction "VO_3") (pintype "input"))
    )
    (net (code "49") (name "/XIN") (class "Default")
      (node (ref "C1") (pin "1") (pinfunction "1_1") (pintype "passive"))
      (node (ref "IC2") (pin "8") (pinfunction "8_8") (pintype "input"))
      (node (ref "Q2") (pin "1") (pinfunction "1_1") (pintype "passive"))
      (node (ref "Q3") (pin "2") (pinfunction "2_2") (pintype "passive"))
      (node (ref "R1") (pin "2") (pinfunction "2_2") (pintype "passive"))
    )
    (net (code "50") (name "/XOUT") (class "Default")
      (node (ref "C2") (pin "1") (pinfunction "1_1") (pintype "passive"))
      (node (ref "IC2") (pin "9") (pinfunction "9_9") (pintype "bidirectional"))
      (node (ref "Q2") (pin "2") (pinfunction "2_2") (pintype "passive"))
      (node (ref "Q3") (pin "1") (pinfunction "1_1") (pintype "passive"))
      (node (ref "R1") (pin "1") (pinfunction "1_1") (pintype "passive"))
    )
    (net (code "51") (name "/XT2IN") (class "Default")
      (node (ref "C18") (pin "1") (pinfunction "1_1") (pintype "passive"))
      (node (ref "IC2") (pin "53") (pinfunction "53_53") (pintype "input"))
      (node (ref "Q1") (pin "2") (pinfunction "2_2") (pintype "passive"))
      (node (ref "R10") (pin "1") (pinfunction "1_1") (pintype "passive"))
    )
    (net (code "52") (name "/XT2OUT") (class "Default")
      (node (ref "C17") (pin "1") (pinfunction "1_1") (pintype "passive"))
      (node (ref "IC2") (pin "52") (pinfunction "52_52") (pintype "output"))
      (node (ref "Q1") (pin "1") (pinfunction "1_1") (pintype "passive"))
      (node (ref "R10") (pin "2") (pinfunction "2_2") (pintype "passive"))
    )
    (net (code "53") (name "GND") (class "Default")
      (node (ref "3.3V") (pin "C") (pinfunction "C_C") (pintype "passive"))
      (node (ref "C1") (pin "2") (pinfunction "2_2") (pintype "passive"))
      (node (ref "C10") (pin "-") (pinfunction "-_-") (pintype "passive"))
      (node (ref "C11") (pin "-") (pinfunction "-_-") (pintype "passive"))
      (node (ref "C12") (pin "-") (pinfunction "-_-") (pintype "passive"))
      (node (ref "C13") (pin "1") (pinfunction "1_1") (pintype "passive"))
      (node (ref "C15") (pin "2") (pinfunction "2_2") (pintype "passive"))
      (node (ref "C16") (pin "2") (pinfunction "2_2") (pintype "passive"))
      (node (ref "C17") (pin "2") (pinfunction "2_2") (pintype "passive"))
      (node (ref "C18") (pin "2") (pinfunction "2_2") (pintype "passive"))
      (node (ref "C19") (pin "2") (pinfunction "2_2") (pintype "passive"))
      (node (ref "C2") (pin "2") (pinfunction "2_2") (pintype "passive"))
      (node (ref "C20") (pin "+") (pinfunction "+_+") (pintype "passive"))
      (node (ref "C21") (pin "1") (pinfunction "1_1") (pintype "passive"))
      (node (ref "C22") (pin "1") (pinfunction "1_1") (pintype "passive"))
      (node (ref "C23") (pin "1") (pinfunction "1_1") (pintype "passive"))
      (node (ref "C24") (pin "1") (pinfunction "1_1") (pintype "passive"))
      (node (ref "C26") (pin "2") (pinfunction "2_2") (pintype "passive"))
      (node (ref "C27") (pin "2") (pinfunction "2_2") (pintype "passive"))
      (node (ref "C28") (pin "2") (pinfunction "2_2") (pintype "passive"))
      (node (ref "C3") (pin "2") (pinfunction "2_2") (pintype "passive"))
      (node (ref "C31") (pin "2") (pinfunction "2_2") (pintype "passive"))
      (node (ref "C4") (pin "-") (pinfunction "-_-") (pintype "passive"))
      (node (ref "C5") (pin "-") (pinfunction "-_-") (pintype "passive"))
      (node (ref "C6") (pin "-") (pinfunction "-_-") (pintype "passive"))
      (node (ref "C7") (pin "2") (pinfunction "2_2") (pintype "passive"))
      (node (ref "C8") (pin "1") (pinfunction "1_1") (pintype "passive"))
      (node (ref "C9") (pin "2") (pinfunction "2_2") (pintype "passive"))
      (node (ref "D2") (pin "A") (pinfunction "A_A") (pintype "passive"))
      (node (ref "D3") (pin "A") (pinfunction "A_A") (pintype "passive"))
      (node (ref "D4") (pin "A") (pinfunction "A_A") (pintype "passive"))
      (node (ref "IC1") (pin "18") (pinfunction "GND18_18") (pintype "power_in"))
      (node (ref "IC1") (pin "21") (pinfunction "GND21_21") (pintype "power_in"))
      (node (ref "IC1") (pin "25") (pinfunction "AGND_25") (pintype "power_in"))
      (node (ref "IC1") (pin "26") (pinfunction "TEST_26") (pintype "input"))
      (node (ref "IC1") (pin "7") (pinfunction "GND7_7") (pintype "power_in"))
      (node (ref "IC2") (pin "11") (pinfunction "11_11") (pintype "bidirectional"))
      (node (ref "IC2") (pin "62") (pinfunction "62_62") (pintype "power_in"))
      (node (ref "IC2") (pin "63") (pinfunction "63_63") (pintype "power_in"))
      (node (ref "J5") (pin "1") (pinfunction "1_1") (pintype "bidirectional"))
      (node (ref "JP5") (pin "3") (pinfunction "3_3") (pintype "passive"))
      (node (ref "R11") (pin "1") (pinfunction "A_1") (pintype "passive"))
      (node (ref "R11") (pin "2") (pinfunction "S_2") (pintype "passive"))
      (node (ref "R12") (pin "1") (pinfunction "A_1") (pintype "passive"))
      (node (ref "R12") (pin "2") (pinfunction "S_2") (pintype "passive"))
      (node (ref "R16") (pin "1") (pinfunction "A_1") (pintype "passive"))
      (node (ref "R16") (pin "2") (pinfunction "S_2") (pintype "passive"))
      (node (ref "R18") (pin "2") (pinfunction "2_2") (pintype "passive"))
      (node (ref "R20") (pin "2") (pinfunction "2_2") (pintype "passive"))
      (node (ref "R24") (pin "1") (pinfunction "A_1") (pintype "passive"))
      (node (ref "R26") (pin "1") (pinfunction "A_1") (pintype "passive"))
      (node (ref "R26") (pin "2") (pinfunction "S_2") (pintype "passive"))
      (node (ref "R27") (pin "2") (pinfunction "2_2") (pintype "passive"))
      (node (ref "R28") (pin "1") (pinfunction "1_1") (pintype "passive"))
      (node (ref "R31") (pin "1") (pinfunction "1_1") (pintype "passive"))
      (node (ref "R31") (pin "2") (pinfunction "2_2") (pintype "passive"))
      (node (ref "R7") (pin "1") (pinfunction "A_1") (pintype "passive"))
      (node (ref "R7") (pin "2") (pinfunction "S_2") (pintype "passive"))
      (node (ref "RESET") (pin "1") (pinfunction "1_1") (pintype "passive"))
      (node (ref "SG1") (pin "-") (pinfunction "2_-") (pintype "passive"))
      (node (ref "SV2") (pin "9") (pinfunction "9_9") (pintype "passive"))
      (node (ref "SV3") (pin "1") (pinfunction "1_1") (pintype "passive"))
      (node (ref "SV4") (pin "4") (pinfunction "4_4") (pintype "passive"))
      (node (ref "U$2") (pin "1") (pinfunction "VSS_1") (pintype "power_in"))
      (node (ref "U$2") (pin "16") (pinfunction "K_16") (pintype "input"))
      (node (ref "U1") (pin "1") (pinfunction "P$1_1") (pintype "bidirectional"))
      (node (ref "U2") (pin "2") (pinfunction "GND_2") (pintype "bidirectional"))
      (node (ref "U3") (pin "2") (pinfunction "GND_2") (pintype "bidirectional"))
      (node (ref "X2") (pin "GND") (pinfunction "GND_GND") (pintype "bidirectional"))
    )
    (net (code "54") (name "Net-(3.3V-PadA)") (class "Default")
      (node (ref "3.3V") (pin "A") (pinfunction "A_A") (pintype "passive"))
      (node (ref "R4") (pin "1") (pinfunction "1_1") (pintype "passive"))
    )
    (net (code "55") (name "Net-(D1--)") (class "Default")
      (node (ref "D1") (pin "C") (pinfunction "-_C") (pintype "passive"))
      (node (ref "F1") (pin "1") (pinfunction "1_1") (pintype "bidirectional"))
    )
    (net (code "56") (name "Net-(F1-Pad2)") (class "Default")
      (node (ref "F1") (pin "2") (pinfunction "2_2") (pintype "bidirectional"))
      (node (ref "L1") (pin "2") (pinfunction "2_2") (pintype "passive"))
    )
    (net (code "57") (name "Net-(FB1-P$2)") (class "Default")
      (node (ref "C6") (pin "+") (pinfunction "+_+") (pintype "passive"))
      (node (ref "C7") (pin "1") (pinfunction "1_1") (pintype "passive"))
      (node (ref "FB1") (pin "2") (pinfunction "P$2_2") (pintype "passive"))
      (node (ref "IC2") (pin "64") (pinfunction "64_64") (pintype "power_in"))
    )
    (net (code "58") (name "Net-(IC1-RXLED)") (class "Default")
      (node (ref "IC1") (pin "22") (pinfunction "RXLED_22") (pintype "input"))
      (node (ref "RX") (pin "C") (pinfunction "C_C") (pintype "passive"))
    )
    (net (code "59") (name "Net-(IC1-TXLED)") (class "Default")
      (node (ref "IC1") (pin "23") (pinfunction "TXLED_23") (pintype "input"))
      (node (ref "TX") (pin "C") (pinfunction "C_C") (pintype "passive"))
    )
    (net (code "60") (name "Net-(IC2-Pad28)") (class "Default")
      (node (ref "IC2") (pin "28") (pinfunction "28_28") (pintype "bidirectional"))
      (node (ref "SV1") (pin "4") (pinfunction "4_4") (pintype "passive"))
    )
    (net (code "61") (name "Net-(IC2-Pad29)") (class "Default")
      (node (ref "IC2") (pin "29") (pinfunction "29_29") (pintype "bidirectional"))
      (node (ref "SV1") (pin "3") (pinfunction "3_3") (pintype "passive"))
    )
    (net (code "62") (name "Net-(IC2-Pad30)") (class "Default")
      (node (ref "IC2") (pin "30") (pinfunction "30_30") (pintype "bidirectional"))
      (node (ref "SV1") (pin "2") (pinfunction "2_2") (pintype "passive"))
    )
    (net (code "63") (name "Net-(IC2-Pad31)") (class "Default")
      (node (ref "IC2") (pin "31") (pinfunction "31_31") (pintype "bidirectional"))
      (node (ref "SV1") (pin "1") (pinfunction "1_1") (pintype "passive"))
    )
    (net (code "64") (name "Net-(IC2-Pad36)") (class "Default")
      (node (ref "IC2") (pin "36") (pinfunction "36_36") (pintype "output"))
      (node (ref "JP1") (pin "4") (pinfunction "4_4") (pintype "passive"))
    )
    (net (code "65") (name "Net-(IC2-Pad37)") (class "Default")
      (node (ref "IC2") (pin "37") (pinfunction "37_37") (pintype "bidirectional"))
      (node (ref "JP1") (pin "3") (pinfunction "3_3") (pintype "passive"))
    )
    (net (code "66") (name "Net-(IC2-Pad38)") (class "Default")
      (node (ref "IC2") (pin "38") (pinfunction "38_38") (pintype "bidirectional"))
      (node (ref "JP1") (pin "2") (pinfunction "2_2") (pintype "passive"))
    )
    (net (code "67") (name "Net-(IC2-Pad39)") (class "Default")
      (node (ref "IC2") (pin "39") (pinfunction "39_39") (pintype "bidirectional"))
      (node (ref "JP1") (pin "1") (pinfunction "1_1") (pintype "passive"))
    )
    (net (code "68") (name "Net-(IC2-Pad40)") (class "Default")
      (node (ref "IC2") (pin "40") (pinfunction "40_40") (pintype "input"))
      (node (ref "JP2") (pin "4") (pinfunction "4_4") (pintype "passive"))
    )
    (net (code "69") (name "Net-(IC2-Pad41)") (class "Default")
      (node (ref "IC2") (pin "41") (pinfunction "41_41") (pintype "bidirectional"))
      (node (ref "JP2") (pin "3") (pinfunction "3_3") (pintype "passive"))
    )
    (net (code "70") (name "Net-(IC2-Pad42)") (class "Default")
      (node (ref "IC2") (pin "42") (pinfunction "42_42") (pintype "bidirectional"))
      (node (ref "JP2") (pin "2") (pinfunction "2_2") (pintype "passive"))
    )
    (net (code "71") (name "Net-(IC2-Pad44)") (class "Default")
      (node (ref "IC2") (pin "44") (pinfunction "44_44") (pintype "bidirectional"))
      (node (ref "JP3") (pin "4") (pinfunction "4_4") (pintype "passive"))
    )
    (net (code "72") (name "Net-(IC2-Pad45)") (class "Default")
      (node (ref "IC2") (pin "45") (pinfunction "45_45") (pintype "bidirectional"))
      (node (ref "JP3") (pin "3") (pinfunction "3_3") (pintype "passive"))
    )
    (net (code "73") (name "Net-(IC2-Pad46)") (class "Default")
      (node (ref "IC2") (pin "46") (pinfunction "46_46") (pintype "bidirectional"))
      (node (ref "JP3") (pin "2") (pinfunction "2_2") (pintype "passive"))
    )
    (net (code "74") (name "Net-(J1-Pad1)") (class "Default")
      (node (ref "J1") (pin "1") (pinfunction "1_1") (pintype "bidirectional"))
      (node (ref "J2") (pin "2") (pinfunction "2_2") (pintype "bidirectional"))
    )
    (net (code "75") (name "Net-(J3-Pad1)") (class "Default")
      (node (ref "J3") (pin "1") (pinfunction "1_1") (pintype "bidirectional"))
      (node (ref "J4") (pin "2") (pinfunction "2_2") (pintype "bidirectional"))
    )
    (net (code "76") (name "Net-(J5-Pad2)") (class "Default")
      (node (ref "J5") (pin "2") (pinfunction "2_2") (pintype "bidirectional"))
      (node (ref "R29") (pin "1") (pinfunction "1_1") (pintype "passive"))
    )
    (net (code "77") (name "Net-(R3-Pad2)") (class "Default")
      (node (ref "R3") (pin "2") (pinfunction "2_2") (pintype "passive"))
      (node (ref "T1") (pin "B") (pinfunction "B_B") (pintype "passive"))
    )
    (net (code "78") (name "Net-(R12-E)") (class "Default")
      (node (ref "R12") (pin "3") (pinfunction "E_3") (pintype "passive"))
      (node (ref "R9") (pin "1") (pinfunction "1_1") (pintype "passive"))
    )
    (net (code "79") (name "Net-(R13-Pad1)") (class "Default")
      (node (ref "R13") (pin "1") (pinfunction "1_1") (pintype "passive"))
      (node (ref "X2") (pin "D-") (pinfunction "D-_D-") (pintype "bidirectional"))
    )
    (net (code "80") (name "Net-(R14-Pad1)") (class "Default")
      (node (ref "R14") (pin "1") (pinfunction "1_1") (pintype "passive"))
      (node (ref "X2") (pin "D+") (pinfunction "D+_D+") (pintype "bidirectional"))
    )
    (net (code "81") (name "Net-(R16-E)") (class "Default")
      (node (ref "R16") (pin "3") (pinfunction "E_3") (pintype "passive"))
      (node (ref "R8") (pin "1") (pinfunction "1_1") (pintype "passive"))
    )
    (net (code "82") (name "Net-(R19-1)") (class "Default")
      (node (ref "J3") (pin "2") (pinfunction "2_2") (pintype "bidirectional"))
      (node (ref "R15") (pin "2") (pinfunction "2_2") (pintype "passive"))
      (node (ref "R17") (pin "1") (pinfunction "1_1") (pintype "passive"))
      (node (ref "R19") (pin "P$1") (pinfunction "1_P$1") (pintype "passive"))
      (node (ref "U3") (pin "3") (pinfunction "VIN+_3") (pintype "bidirectional"))
    )
    (net (code "83") (name "Net-(R19-2)") (class "Default")
      (node (ref "J4") (pin "1") (pinfunction "1_1") (pintype "bidirectional"))
      (node (ref "R17") (pin "2") (pinfunction "2_2") (pintype "passive"))
      (node (ref "R19") (pin "P$2") (pinfunction "2_P$2") (pintype "passive"))
      (node (ref "U3") (pin "4") (pinfunction "VIN-_4") (pintype "bidirectional"))
    )
    (net (code "84") (name "Net-(R21-Pad2)") (class "Default")
      (node (ref "R21") (pin "2") (pinfunction "2_2") (pintype "passive"))
      (node (ref "RX") (pin "A") (pinfunction "A_A") (pintype "passive"))
    )
    (net (code "85") (name "Net-(R22-Pad2)") (class "Default")
      (node (ref "R22") (pin "2") (pinfunction "2_2") (pintype "passive"))
      (node (ref "TX") (pin "A") (pinfunction "A_A") (pintype "passive"))
    )
    (net (code "86") (name "Net-(R23-Pad2)") (class "Default")
      (node (ref "R23") (pin "2") (pinfunction "2_2") (pintype "passive"))
      (node (ref "SJ1") (pin "2") (pinfunction "2_2") (pintype "passive"))
    )
    (net (code "87") (name "Net-(SG1-1)") (class "Default")
      (node (ref "SG1") (pin "+") (pinfunction "1_+") (pintype "passive"))
      (node (ref "T1") (pin "C") (pinfunction "C_C") (pintype "passive"))
    )
    (net (code "88") (name "Net-(U$2-A)") (class "Default")
      (node (ref "R23") (pin "1") (pinfunction "1_1") (pintype "passive"))
      (node (ref "U$2") (pin "15") (pinfunction "A_15") (pintype "input"))
    )
    (net (code "89") (name "SHUNT1_I") (class "Default")
      (node (ref "C15") (pin "1") (pinfunction "1_1") (pintype "passive"))
      (node (ref "IC2") (pin "5") (pinfunction "5_5") (pintype "bidirectional"))
      (node (ref "R8") (pin "2") (pinfunction "2_2") (pintype "passive"))
      (node (ref "U2") (pin "1") (pinfunction "OUT_1") (pintype "bidirectional"))
    )
    (net (code "90") (name "SHUNT1_V") (class "Default")
      (node (ref "C27") (pin "1") (pinfunction "1_1") (pintype "passive"))
      (node (ref "D2") (pin "C") (pinfunction "C_C") (pintype "passive"))
      (node (ref "IC2") (pin "6") (pinfunction "6_6") (pintype "bidirectional"))
      (node (ref "R11") (pin "3") (pinfunction "E_3") (pintype "passive"))
      (node (ref "R25") (pin "1") (pinfunction "1_1") (pintype "passive"))
    )
    (net (code "91") (name "SHUNT2_I") (class "Default")
      (node (ref "C26") (pin "1") (pinfunction "1_1") (pintype "passive"))
      (node (ref "IC2") (pin "3") (pinfunction "3_3") (pintype "bidirectional"))
      (node (ref "R9") (pin "2") (pinfunction "2_2") (pintype "passive"))
      (node (ref "U3") (pin "1") (pinfunction "OUT_1") (pintype "bidirectional"))
    )
    (net (code "92") (name "SHUNT2_V") (class "Default")
      (node (ref "C28") (pin "1") (pinfunction "1_1") (pintype "passive"))
      (node (ref "D3") (pin "C") (pinfunction "C_C") (pintype "passive"))
      (node (ref "IC2") (pin "4") (pinfunction "4_4") (pintype "bidirectional"))
      (node (ref "R15") (pin "1") (pinfunction "1_1") (pintype "passive"))
      (node (ref "R26") (pin "3") (pinfunction "E_3") (pintype "passive"))
    )
    (net (code "93") (name "VIN") (class "Default")
      (node (ref "D1") (pin "A") (pinfunction "+_A") (pintype "passive"))
      (node (ref "SV3") (pin "3") (pinfunction "3_3") (pintype "passive"))
      (node (ref "X2") (pin "VBUS") (pinfunction "VBUS_VBUS") (pintype "bidirectional"))
    )
    (net (code "94") (name "unconnected-(H1-Pad1)") (class "Default")
      (node (ref "H1") (pin "1") (pinfunction "1_1") (pintype "passive"))
    )
    (net (code "95") (name "unconnected-(H2-Pad1)") (class "Default")
      (node (ref "H2") (pin "1") (pinfunction "1_1") (pintype "passive"))
    )
    (net (code "96") (name "unconnected-(H3-Pad1)") (class "Default")
      (node (ref "H3") (pin "1") (pinfunction "1_1") (pintype "passive"))
    )
    (net (code "97") (name "unconnected-(H4-Pad1)") (class "Default")
      (node (ref "H4") (pin "1") (pinfunction "1_1") (pintype "passive"))
    )
    (net (code "98") (name "unconnected-(H5-Pad1)") (class "Default")
      (node (ref "H5") (pin "1") (pinfunction "1_1") (pintype "passive"))
    )
    (net (code "99") (name "unconnected-(H6-Pad1)") (class "Default")
      (node (ref "H6") (pin "1") (pinfunction "1_1") (pintype "passive"))
    )
    (net (code "100") (name "unconnected-(H7-Pad1)") (class "Default")
      (node (ref "H7") (pin "1") (pinfunction "1_1") (pintype "passive"))
    )
    (net (code "101") (name "unconnected-(H8-Pad1)") (class "Default")
      (node (ref "H8") (pin "1") (pinfunction "1_1") (pintype "passive"))
    )
    (net (code "102") (name "unconnected-(IC1-CTS-Pad11)") (class "Default")
      (node (ref "IC1") (pin "11") (pinfunction "CTS_11") (pintype "input"))
    )
    (net (code "103") (name "unconnected-(IC1-DCD-Pad10)") (class "Default")
      (node (ref "IC1") (pin "10") (pinfunction "DCD_10") (pintype "input"))
    )
    (net (code "104") (name "unconnected-(IC1-DSR-Pad9)") (class "Default")
      (node (ref "IC1") (pin "9") (pinfunction "DSR_9") (pintype "input"))
    )
    (net (code "105") (name "unconnected-(IC1-DTR-Pad2)") (class "Default")
      (node (ref "IC1") (pin "2") (pinfunction "DTR_2") (pintype "output"))
    )
    (net (code "106") (name "unconnected-(IC1-OSCI-Pad27)") (class "Default")
      (node (ref "IC1") (pin "27") (pinfunction "OSCI_27") (pintype "input"))
    )
    (net (code "107") (name "unconnected-(IC1-OSCO-Pad28)") (class "Default")
      (node (ref "IC1") (pin "28") (pinfunction "OSCO_28") (pintype "output"))
    )
    (net (code "108") (name "unconnected-(IC1-RESET-Pad19)") (class "Default")
      (node (ref "IC1") (pin "19") (pinfunction "RESET_19") (pintype "input"))
    )
    (net (code "109") (name "unconnected-(IC1-RI-Pad6)") (class "Default")
      (node (ref "IC1") (pin "6") (pinfunction "RI_6") (pintype "input"))
    )
    (net (code "110") (name "unconnected-(IC1-RTS-Pad3)") (class "Default")
      (node (ref "IC1") (pin "3") (pinfunction "RTS_3") (pintype "output"))
    )
    (net (code "111") (name "unconnected-(IC1-SLEEP-Pad12)") (class "Default")
      (node (ref "IC1") (pin "12") (pinfunction "SLEEP_12") (pintype "input"))
    )
    (net (code "112") (name "unconnected-(IC1-TXDEN-Pad13)") (class "Default")
      (node (ref "IC1") (pin "13") (pinfunction "TXDEN_13") (pintype "input"))
    )
    (net (code "113") (name "unconnected-(SV2-Pad6)") (class "Default")
      (node (ref "SV2") (pin "6") (pinfunction "6_6") (pintype "passive"))
    )
    (net (code "114") (name "unconnected-(SV2-Pad10)") (class "Default")
      (node (ref "SV2") (pin "10") (pinfunction "10_10") (pintype "passive"))
    )
    (net (code "115") (name "unconnected-(SV2-Pad12)") (class "Default")
      (node (ref "SV2") (pin "12") (pinfunction "12_12") (pintype "passive"))
    )
    (net (code "116") (name "unconnected-(SV2-Pad13)") (class "Default")
      (node (ref "SV2") (pin "13") (pinfunction "13_13") (pintype "passive"))
    )
    (net (code "117") (name "unconnected-(SV2-Pad14)") (class "Default")
      (node (ref "SV2") (pin "14") (pinfunction "14_14") (pintype "passive"))
    )
  )
)
